# SCH_Macropad-rev2_2024-06-18.net
KiCad netlist of a schematic drawn in EasyEDA
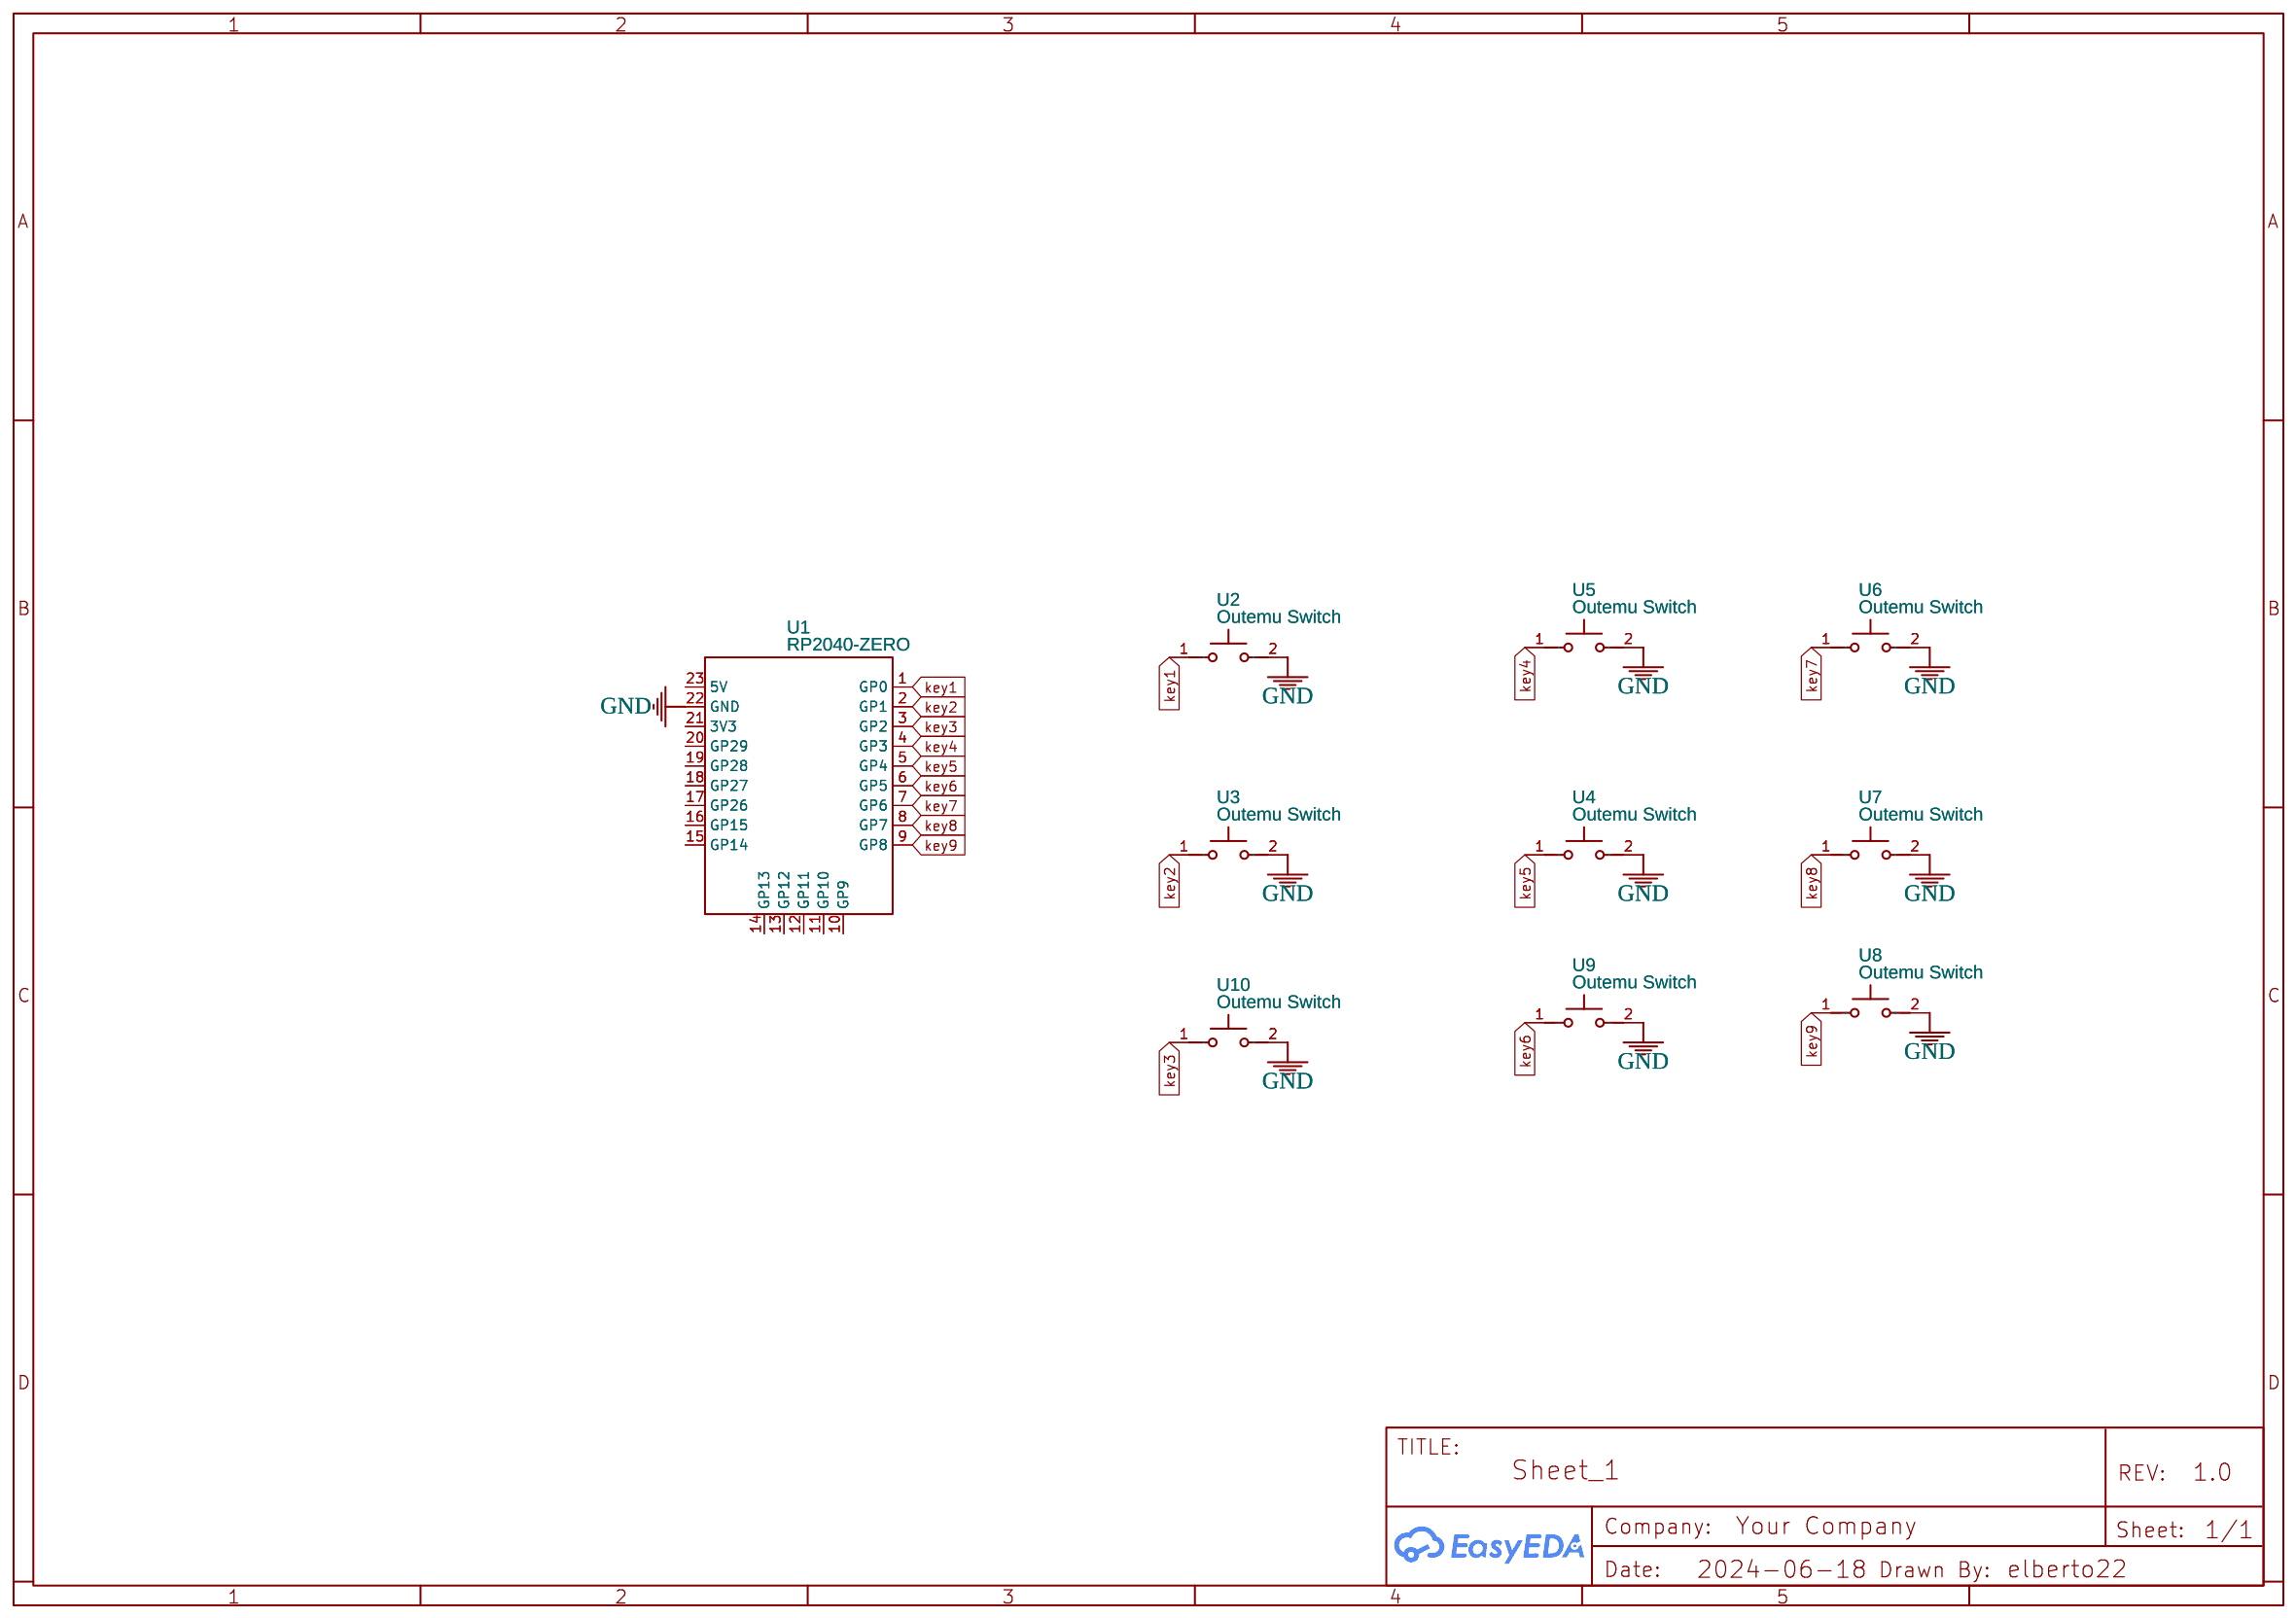
[diagram p0: schematic sheet]

(export (version "E")
  (design (tool "Eeschema 10.0.6"))
  (components
    (comp (ref "U1")
      (value "RP2040-ZERO")
      (fields
        (field (name "Manufacturer Part") "RP2040-Zero")
        (field (name "Manufacturer") "Waveshare(微雪电子)")
      )
      (libsource (lib "") (part "RP2040-ZERO"))
    )
    (comp (ref "U2")
      (value "Outemu Switch")
      (fields (field (name "Manufacturer") "HepLer"))
      (libsource (lib "") (part "Outemu Switch"))
    )
    (comp (ref "U3")
      (value "Outemu Switch")
      (fields (field (name "Manufacturer") "HepLer"))
      (libsource (lib "") (part "Outemu Switch"))
    )
    (comp (ref "U4")
      (value "Outemu Switch")
      (fields (field (name "Manufacturer") "HepLer"))
      (libsource (lib "") (part "Outemu Switch"))
    )
    (comp (ref "U5")
      (value "Outemu Switch")
      (fields (field (name "Manufacturer") "HepLer"))
      (libsource (lib "") (part "Outemu Switch"))
    )
    (comp (ref "U6")
      (value "Outemu Switch")
      (fields (field (name "Manufacturer") "HepLer"))
      (libsource (lib "") (part "Outemu Switch"))
    )
    (comp (ref "U7")
      (value "Outemu Switch")
      (fields (field (name "Manufacturer") "HepLer"))
      (libsource (lib "") (part "Outemu Switch"))
    )
    (comp (ref "U8")
      (value "Outemu Switch")
      (fields (field (name "Manufacturer") "HepLer"))
      (libsource (lib "") (part "Outemu Switch"))
    )
    (comp (ref "U9")
      (value "Outemu Switch")
      (fields (field (name "Manufacturer") "HepLer"))
      (libsource (lib "") (part "Outemu Switch"))
    )
    (comp (ref "U10")
      (value "Outemu Switch")
      (fields (field (name "Manufacturer") "HepLer"))
      (libsource (lib "") (part "Outemu Switch"))
    )
  )
  (nets
    (net (code "1") (name "GND") (class "Default")
      (node (ref "U1") (pin "22") (pinfunction "GND_22") (pintype "unspecified"))
      (node (ref "U10") (pin "2") (pinfunction "2_2") (pintype "unspecified"))
      (node (ref "U2") (pin "2") (pinfunction "2_2") (pintype "unspecified"))
      (node (ref "U3") (pin "2") (pinfunction "2_2") (pintype "unspecified"))
      (node (ref "U4") (pin "2") (pinfunction "2_2") (pintype "unspecified"))
      (node (ref "U5") (pin "2") (pinfunction "2_2") (pintype "unspecified"))
      (node (ref "U6") (pin "2") (pinfunction "2_2") (pintype "unspecified"))
      (node (ref "U7") (pin "2") (pinfunction "2_2") (pintype "unspecified"))
      (node (ref "U8") (pin "2") (pinfunction "2_2") (pintype "unspecified"))
      (node (ref "U9") (pin "2") (pinfunction "2_2") (pintype "unspecified"))
    )
    (net (code "2") (name "key1") (class "Default")
      (node (ref "U1") (pin "1") (pinfunction "GP0_1") (pintype "unspecified"))
      (node (ref "U2") (pin "1") (pinfunction "1_1") (pintype "unspecified"))
    )
    (net (code "3") (name "key2") (class "Default")
      (node (ref "U1") (pin "2") (pinfunction "GP1_2") (pintype "unspecified"))
      (node (ref "U3") (pin "1") (pinfunction "1_1") (pintype "unspecified"))
    )
    (net (code "4") (name "key3") (class "Default")
      (node (ref "U1") (pin "3") (pinfunction "GP2_3") (pintype "unspecified"))
      (node (ref "U10") (pin "1") (pinfunction "1_1") (pintype "unspecified"))
    )
    (net (code "5") (name "key4") (class "Default")
      (node (ref "U1") (pin "4") (pinfunction "GP3_4") (pintype "unspecified"))
      (node (ref "U5") (pin "1") (pinfunction "1_1") (pintype "unspecified"))
    )
    (net (code "6") (name "key5") (class "Default")
      (node (ref "U1") (pin "5") (pinfunction "GP4_5") (pintype "unspecified"))
      (node (ref "U4") (pin "1") (pinfunction "1_1") (pintype "unspecified"))
    )
    (net (code "7") (name "key6") (class "Default")
      (node (ref "U1") (pin "6") (pinfunction "GP5_6") (pintype "unspecified"))
      (node (ref "U9") (pin "1") (pinfunction "1_1") (pintype "unspecified"))
    )
    (net (code "8") (name "key7") (class "Default")
      (node (ref "U1") (pin "7") (pinfunction "GP6_7") (pintype "unspecified"))
      (node (ref "U6") (pin "1") (pinfunction "1_1") (pintype "unspecified"))
    )
    (net (code "9") (name "key8") (class "Default")
      (node (ref "U1") (pin "8") (pinfunction "GP7_8") (pintype "unspecified"))
      (node (ref "U7") (pin "1") (pinfunction "1_1") (pintype "unspecified"))
    )
    (net (code "10") (name "key9") (class "Default")
      (node (ref "U1") (pin "9") (pinfunction "GP8_9") (pintype "unspecified"))
      (node (ref "U8") (pin "1") (pinfunction "1_1") (pintype "unspecified"))
    )
    (net (code "11") (name "unconnected-(U1-3V3-Pad21)") (class "Default")
      (node (ref "U1") (pin "21") (pinfunction "3V3_21") (pintype "unspecified"))
    )
    (net (code "12") (name "unconnected-(U1-5V-Pad23)") (class "Default")
      (node (ref "U1") (pin "23") (pinfunction "5V_23") (pintype "unspecified"))
    )
    (net (code "13") (name "unconnected-(U1-GP9-Pad10)") (class "Default")
      (node (ref "U1") (pin "10") (pinfunction "GP9_10") (pintype "unspecified"))
    )
    (net (code "14") (name "unconnected-(U1-GP10-Pad11)") (class "Default")
      (node (ref "U1") (pin "11") (pinfunction "GP10_11") (pintype "unspecified"))
    )
    (net (code "15") (name "unconnected-(U1-GP11-Pad12)") (class "Default")
      (node (ref "U1") (pin "12") (pinfunction "GP11_12") (pintype "unspecified"))
    )
    (net (code "16") (name "unconnected-(U1-GP12-Pad13)") (class "Default")
      (node (ref "U1") (pin "13") (pinfunction "GP12_13") (pintype "unspecified"))
    )
    (net (code "17") (name "unconnected-(U1-GP13-Pad14)") (class "Default")
      (node (ref "U1") (pin "14") (pinfunction "GP13_14") (pintype "unspecified"))
    )
    (net (code "18") (name "unconnected-(U1-GP14-Pad15)") (class "Default")
      (node (ref "U1") (pin "15") (pinfunction "GP14_15") (pintype "unspecified"))
    )
    (net (code "19") (name "unconnected-(U1-GP15-Pad16)") (class "Default")
      (node (ref "U1") (pin "16") (pinfunction "GP15_16") (pintype "unspecified"))
    )
    (net (code "20") (name "unconnected-(U1-GP26-Pad17)") (class "Default")
      (node (ref "U1") (pin "17") (pinfunction "GP26_17") (pintype "unspecified"))
    )
    (net (code "21") (name "unconnected-(U1-GP27-Pad18)") (class "Default")
      (node (ref "U1") (pin "18") (pinfunction "GP27_18") (pintype "unspecified"))
    )
    (net (code "22") (name "unconnected-(U1-GP28-Pad19)") (class "Default")
      (node (ref "U1") (pin "19") (pinfunction "GP28_19") (pintype "unspecified"))
    )
    (net (code "23") (name "unconnected-(U1-GP29-Pad20)") (class "Default")
      (node (ref "U1") (pin "20") (pinfunction "GP29_20") (pintype "unspecified"))
    )
  )
)
